# rw-directish-17mm-mk-1_5.net
KiCad netlist of a schematic drawn in EAGLE
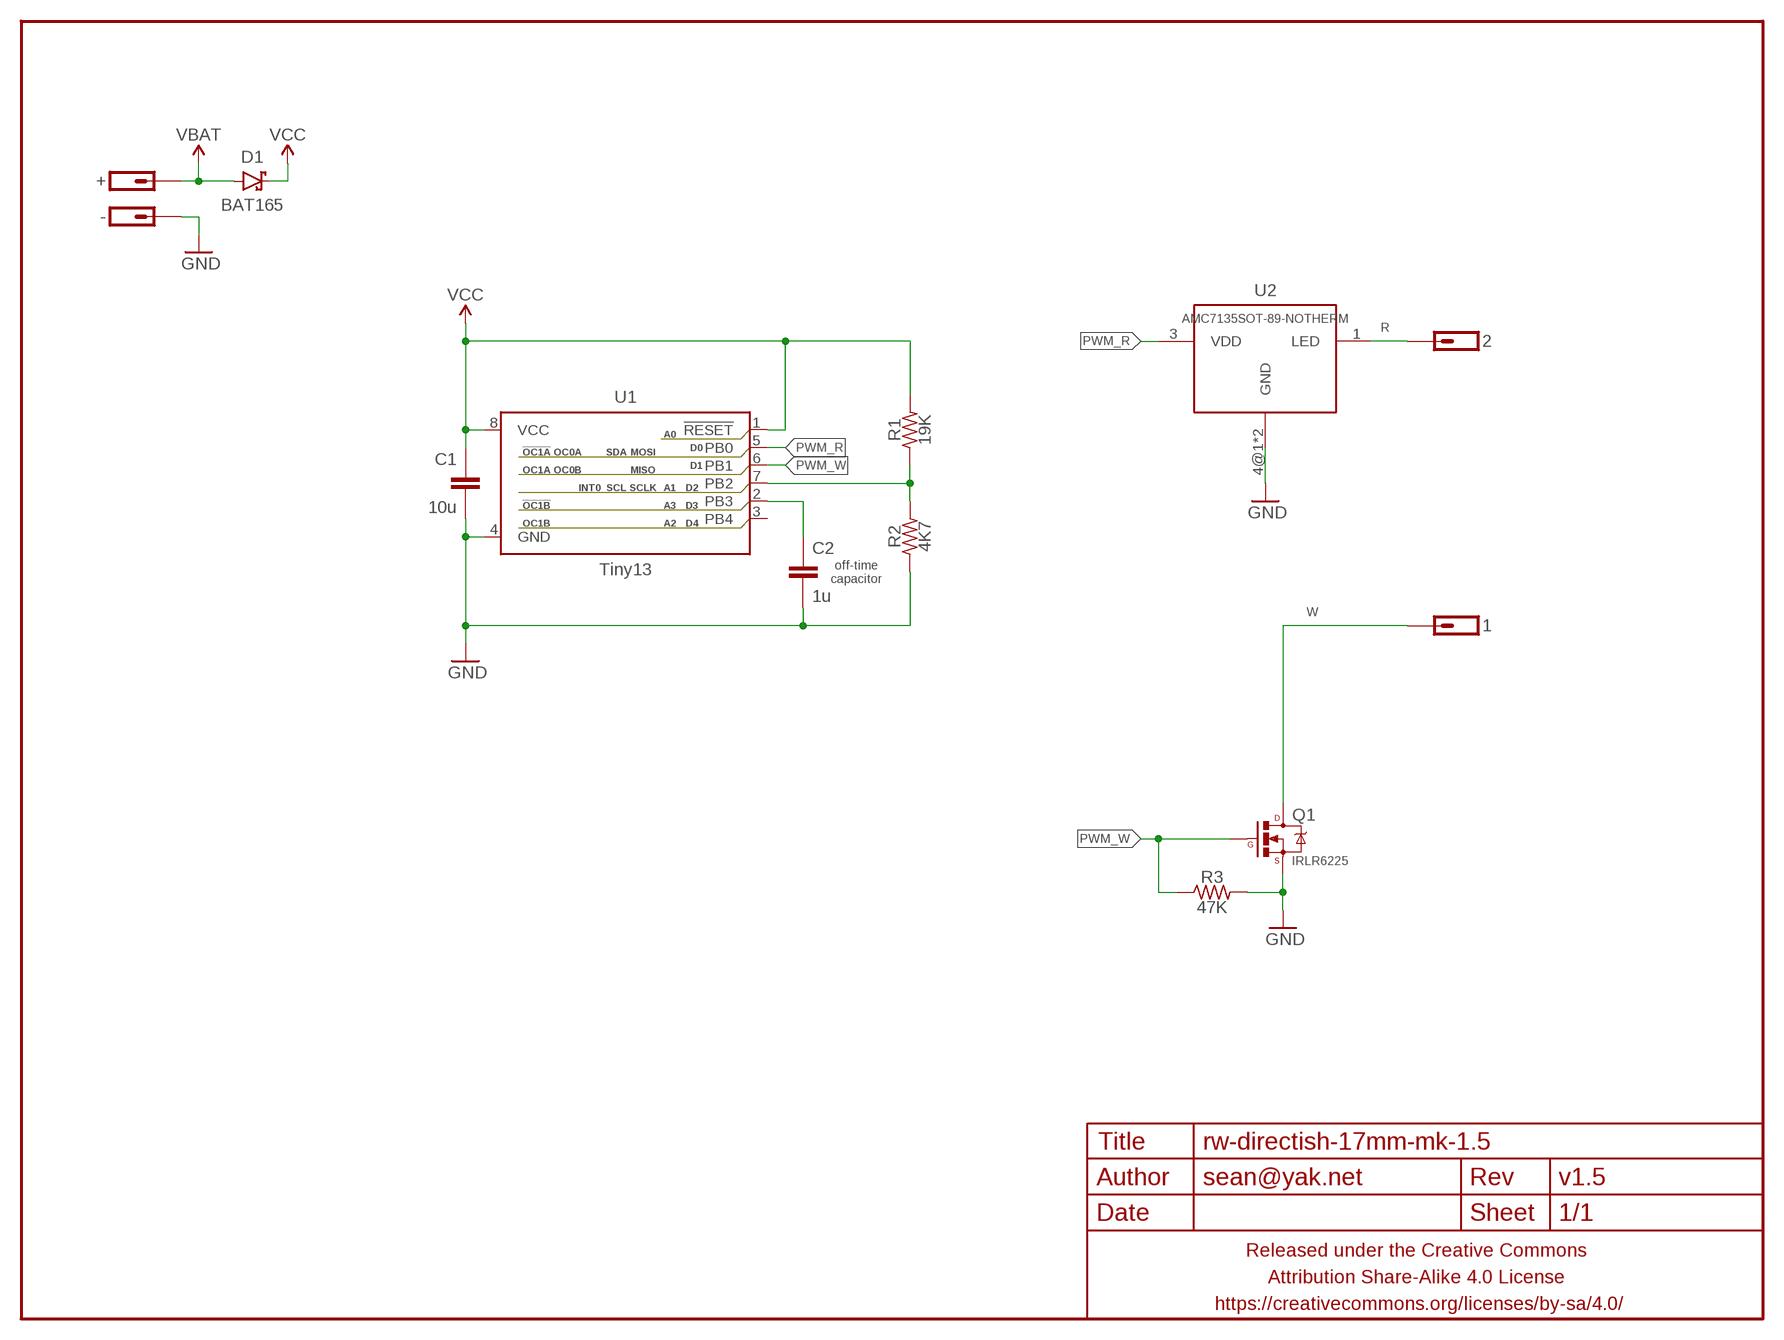
[diagram p0: schematic, sheet 1]

(export (version "E")
  (design (tool "Eeschema 10.0.6"))
  (components
    (comp (ref "+")
      (value "M01PTH-1MM-CIR-NS")
      (footprint "eagle-import:1X01-1MM-CIR-NS")
      (libsource (lib "eagle-import") (part "M01PTH-1MM-CIR-NS"))
    )
    (comp (ref "-")
      (value "M01NOT-A-VIA-NOPE")
      (footprint "eagle-import:1X01_NOSILK_NOSTOP")
      (libsource (lib "eagle-import") (part "M01NOT-A-VIA-NOPE"))
    )
    (comp (ref "1")
      (value "M01SMD-1.25MM-DIA")
      (footprint "eagle-import:1X01-SMD-1.25MM-DIA-NS")
      (libsource (lib "eagle-import") (part "M01SMD-1.25MM-DIA"))
    )
    (comp (ref "2")
      (value "M01SMD-1.25MM-DIA")
      (footprint "eagle-import:1X01-SMD-1.25MM-DIA-NS")
      (libsource (lib "eagle-import") (part "M01SMD-1.25MM-DIA"))
    )
    (comp (ref "C1")
      (value "10u")
      (footprint "eagle-import:C0603-TIGHTER")
      (libsource (lib "eagle-import") (part "CAPACITOR-CERAMICC0603-TIGHTER"))
    )
    (comp (ref "C2")
      (value "1u")
      (footprint "eagle-import:C0402")
      (libsource (lib "eagle-import") (part "CAPACITOR-CERAMICC0402"))
    )
    (comp (ref "D1")
      (value "BAT165")
      (footprint "eagle-import:SOD323-SCHOTTKY")
      (libsource (lib "eagle-import") (part "DIODE-SCHOTTKYSOD323"))
    )
    (comp (ref "FRAME1")
      (value "FRAME-LETTERNO_PACKAGE")
      (footprint "eagle-import:DUMMY")
      (fields (field (name "DESIGNER") "sean@yak.net") (field (name "VERSION") "v1.5"))
      (libsource (lib "eagle-import") (part "FRAME-LETTERNO_PACKAGE"))
    )
    (comp (ref "Q1")
      (value "IRLR6225")
      (footprint "eagle-import:SO08-NARROWER")
      (libsource (lib "eagle-import") (part "MOSFET-NCHANNELSO08-NARROWER"))
    )
    (comp (ref "R1")
      (value "19K")
      (footprint "eagle-import:R0402")
      (libsource (lib "eagle-import") (part "RESISTORR0402"))
    )
    (comp (ref "R2")
      (value "4K7")
      (footprint "eagle-import:R0402")
      (libsource (lib "eagle-import") (part "RESISTORR0402"))
    )
    (comp (ref "R3")
      (value "47K")
      (footprint "eagle-import:R0402")
      (libsource (lib "eagle-import") (part "RESISTORR0402"))
    )
    (comp (ref "U1")
      (value "Tiny13")
      (footprint "eagle-import:SO08-NARROWER")
      (libsource (lib "eagle-import") (part "ATTINY13SOIC-NARROWPADS"))
    )
    (comp (ref "U2")
      (value "AMC7135SOT-89-NOTHERM")
      (footprint "eagle-import:SOT89-NOTHERM")
      (libsource (lib "eagle-import") (part "AMC7135SOT-89-NOTHERM"))
    )
  )
  (nets
    (net (code "1") (name "/R") (class "Default")
      (node (ref "2") (pin "P$1") (pinfunction "1_P$1") (pintype "passive"))
      (node (ref "U2") (pin "1") (pinfunction "LED_1") (pintype "bidirectional"))
    )
    (net (code "2") (name "/W") (class "Default")
      (node (ref "1") (pin "P$1") (pinfunction "1_P$1") (pintype "passive"))
      (node (ref "Q1") (pin "5") (pinfunction "D_5") (pintype "passive"))
      (node (ref "Q1") (pin "6") (pinfunction "D_6") (pintype "passive"))
      (node (ref "Q1") (pin "7") (pinfunction "D_7") (pintype "passive"))
      (node (ref "Q1") (pin "8") (pinfunction "D_8") (pintype "passive"))
    )
    (net (code "3") (name "GND") (class "Default")
      (node (ref "-") (pin "P$1") (pinfunction "1_P$1") (pintype "passive"))
      (node (ref "C1") (pin "2") (pinfunction "2_2") (pintype "passive"))
      (node (ref "C2") (pin "2") (pinfunction "2_2") (pintype "passive"))
      (node (ref "Q1") (pin "1") (pinfunction "S_1") (pintype "passive"))
      (node (ref "Q1") (pin "2") (pinfunction "S_2") (pintype "passive"))
      (node (ref "Q1") (pin "3") (pinfunction "S_3") (pintype "passive"))
      (node (ref "R2") (pin "1") (pinfunction "1_1") (pintype "passive"))
      (node (ref "R3") (pin "2") (pinfunction "2_2") (pintype "passive"))
      (node (ref "U1") (pin "4") (pinfunction "GND_4") (pintype "bidirectional"))
      (node (ref "U2") (pin "4@1") (pinfunction "GND_4@1") (pintype "bidirectional"))
      (node (ref "U2") (pin "4@2") (pinfunction "GND_4@2") (pintype "bidirectional"))
    )
    (net (code "4") (name "Net-(U1-PB2)") (class "Default")
      (node (ref "R1") (pin "1") (pinfunction "1_1") (pintype "passive"))
      (node (ref "R2") (pin "2") (pinfunction "2_2") (pintype "passive"))
      (node (ref "U1") (pin "7") (pinfunction "PB2_7") (pintype "bidirectional"))
    )
    (net (code "5") (name "Net-(U1-PB3)") (class "Default")
      (node (ref "C2") (pin "1") (pinfunction "1_1") (pintype "passive"))
      (node (ref "U1") (pin "2") (pinfunction "PB3_2") (pintype "bidirectional"))
    )
    (net (code "6") (name "PWM_R") (class "Default")
      (node (ref "U1") (pin "5") (pinfunction "PB0_5") (pintype "bidirectional"))
      (node (ref "U2") (pin "3") (pinfunction "VDD_3") (pintype "bidirectional"))
    )
    (net (code "7") (name "PWM_W") (class "Default")
      (node (ref "Q1") (pin "4") (pinfunction "G_4") (pintype "passive"))
      (node (ref "R3") (pin "1") (pinfunction "1_1") (pintype "passive"))
      (node (ref "U1") (pin "6") (pinfunction "PB1_6") (pintype "bidirectional"))
    )
    (net (code "8") (name "VBAT") (class "Default")
      (node (ref "+") (pin "1") (pinfunction "1_1") (pintype "passive"))
      (node (ref "D1") (pin "A") (pinfunction "A_A") (pintype "passive"))
    )
    (net (code "9") (name "VCC") (class "Default")
      (node (ref "C1") (pin "1") (pinfunction "1_1") (pintype "passive"))
      (node (ref "D1") (pin "C") (pinfunction "C_C") (pintype "passive"))
      (node (ref "R1") (pin "2") (pinfunction "2_2") (pintype "passive"))
      (node (ref "U1") (pin "1") (pinfunction "~{RESET}_1") (pintype "bidirectional"))
      (node (ref "U1") (pin "8") (pinfunction "VCC_8") (pintype "bidirectional"))
    )
    (net (code "10") (name "unconnected-(U1-PB4-Pad3)") (class "Default")
      (node (ref "U1") (pin "3") (pinfunction "PB4_3") (pintype "bidirectional"))
    )
  )
)
